# voltage_meas.net
KiCad netlist of a schematic drawn in EAGLE
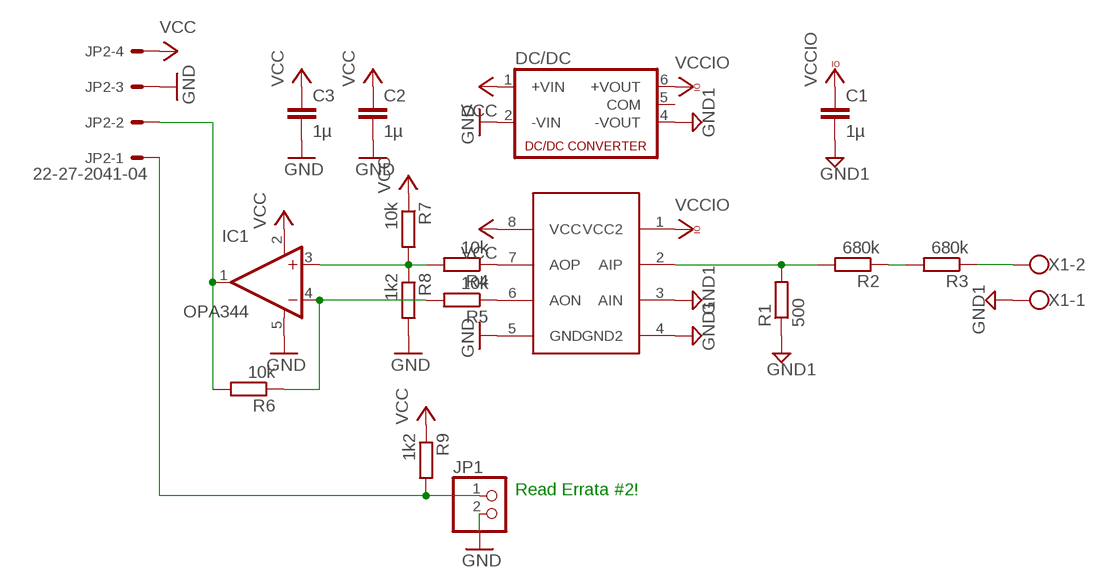
[diagram p0: schematic, sheet 1]

(export (version "E")
  (design (tool "Eeschema 10.0.6"))
  (components
    (comp (ref "C1")
      (value "1µ")
      (footprint "eagle-import:C025-024X044")
      (libsource (lib "eagle-import") (part "C-EU025-024X044"))
    )
    (comp (ref "C2")
      (value "1µ")
      (footprint "eagle-import:C025-024X044")
      (libsource (lib "eagle-import") (part "C-EU025-024X044"))
    )
    (comp (ref "C3")
      (value "1µ")
      (footprint "eagle-import:C025-024X044")
      (libsource (lib "eagle-import") (part "C-EU025-024X044"))
    )
    (comp (ref "DC/DC")
      (value "MEV3")
      (footprint "eagle-import:NMA")
      (libsource (lib "eagle-import") (part "MEV3"))
    )
    (comp (ref "IC1")
      (value "OPA344")
      (footprint "eagle-import:SOT23-5")
      (libsource (lib "eagle-import") (part "OPA344"))
    )
    (comp (ref "IC2")
      (value "SI8920")
      (footprint "eagle-import:DIP8")
      (libsource (lib "eagle-import") (part "SI8920"))
    )
    (comp (ref "JP1")
      (value "PINHD-1X2")
      (footprint "eagle-import:1X02")
      (libsource (lib "eagle-import") (part "PINHD-1X2"))
    )
    (comp (ref "JP2")
      (value "22-27-2041-04")
      (footprint "eagle-import:6410-04")
      (libsource (lib "eagle-import") (part "22-?-0427-2041"))
    )
    (comp (ref "R1")
      (value "500")
      (footprint "eagle-import:0207_10")
      (libsource (lib "eagle-import") (part "R-EU_0207/10"))
    )
    (comp (ref "R2")
      (value "680k")
      (footprint "eagle-import:0207_10")
      (libsource (lib "eagle-import") (part "R-EU_0207/10"))
    )
    (comp (ref "R3")
      (value "680k")
      (footprint "eagle-import:0207_10")
      (libsource (lib "eagle-import") (part "R-EU_0207/10"))
    )
    (comp (ref "R4")
      (value "10k")
      (footprint "eagle-import:0207_10")
      (libsource (lib "eagle-import") (part "R-EU_0207/10"))
    )
    (comp (ref "R5")
      (value "10k")
      (footprint "eagle-import:0207_10")
      (libsource (lib "eagle-import") (part "R-EU_0207/10"))
    )
    (comp (ref "R6")
      (value "10k")
      (footprint "eagle-import:0207_10")
      (libsource (lib "eagle-import") (part "R-EU_0207/10"))
    )
    (comp (ref "R7")
      (value "10k")
      (footprint "eagle-import:0207_10")
      (libsource (lib "eagle-import") (part "R-EU_0207/10"))
    )
    (comp (ref "R8")
      (value "1k2")
      (footprint "eagle-import:0207_10")
      (libsource (lib "eagle-import") (part "R-EU_0207/10"))
    )
    (comp (ref "R9")
      (value "1k2")
      (footprint "eagle-import:0207_10")
      (libsource (lib "eagle-import") (part "R-EU_0207/10"))
    )
    (comp (ref "X1")
      (value "W237-102")
      (footprint "eagle-import:W237-102")
      (fields (field (name "MPN") "237-102"))
      (libsource (lib "eagle-import") (part "W237-102"))
    )
  )
  (nets
    (net (code "1") (name "GND") (class "Default")
      (node (ref "C2") (pin "2") (pinfunction "2_2") (pintype "passive"))
      (node (ref "C3") (pin "2") (pinfunction "2_2") (pintype "passive"))
      (node (ref "DC/DC") (pin "2") (pinfunction "-VIN_2") (pintype "passive"))
      (node (ref "IC1") (pin "5") (pinfunction "V+_5") (pintype "power_in"))
      (node (ref "IC2") (pin "5") (pinfunction "GND_5") (pintype "bidirectional"))
      (node (ref "JP1") (pin "2") (pinfunction "2_2") (pintype "passive"))
      (node (ref "JP2") (pin "3") (pinfunction "S_3") (pintype "passive"))
      (node (ref "R8") (pin "2") (pinfunction "2_2") (pintype "passive"))
    )
    (net (code "2") (name "GND1") (class "Default")
      (node (ref "C1") (pin "2") (pinfunction "2_2") (pintype "passive"))
      (node (ref "DC/DC") (pin "4") (pinfunction "-VOUT_4") (pintype "passive"))
      (node (ref "IC2") (pin "3") (pinfunction "AIN_3") (pintype "bidirectional"))
      (node (ref "IC2") (pin "4") (pinfunction "GND2_4") (pintype "bidirectional"))
      (node (ref "R1") (pin "1") (pinfunction "1_1") (pintype "passive"))
      (node (ref "X1") (pin "1") (pinfunction "KL_1") (pintype "passive"))
    )
    (net (code "3") (name "Net-(IC1-+IN)") (class "Default")
      (node (ref "IC1") (pin "3") (pinfunction "+IN_3") (pintype "input"))
      (node (ref "R4") (pin "2") (pinfunction "2_2") (pintype "passive"))
      (node (ref "R7") (pin "2") (pinfunction "2_2") (pintype "passive"))
      (node (ref "R8") (pin "1") (pinfunction "1_1") (pintype "passive"))
    )
    (net (code "4") (name "Net-(IC1--IN)") (class "Default")
      (node (ref "IC1") (pin "4") (pinfunction "-IN_4") (pintype "input"))
      (node (ref "R5") (pin "2") (pinfunction "2_2") (pintype "passive"))
      (node (ref "R6") (pin "1") (pinfunction "1_1") (pintype "passive"))
    )
    (net (code "5") (name "Net-(IC1-OUT)") (class "Default")
      (node (ref "IC1") (pin "1") (pinfunction "OUT_1") (pintype "output"))
      (node (ref "JP2") (pin "2") (pinfunction "S_2") (pintype "passive"))
      (node (ref "R6") (pin "2") (pinfunction "2_2") (pintype "passive"))
    )
    (net (code "6") (name "Net-(IC2-AIP)") (class "Default")
      (node (ref "IC2") (pin "2") (pinfunction "AIP_2") (pintype "bidirectional"))
      (node (ref "R1") (pin "2") (pinfunction "2_2") (pintype "passive"))
      (node (ref "R2") (pin "2") (pinfunction "2_2") (pintype "passive"))
    )
    (net (code "7") (name "Net-(IC2-AON)") (class "Default")
      (node (ref "IC2") (pin "6") (pinfunction "AON_6") (pintype "bidirectional"))
      (node (ref "R5") (pin "1") (pinfunction "1_1") (pintype "passive"))
    )
    (net (code "8") (name "Net-(IC2-AOP)") (class "Default")
      (node (ref "IC2") (pin "7") (pinfunction "AOP_7") (pintype "bidirectional"))
      (node (ref "R4") (pin "1") (pinfunction "1_1") (pintype "passive"))
    )
    (net (code "9") (name "Net-(JP2A-S)") (class "Default")
      (node (ref "JP1") (pin "1") (pinfunction "1_1") (pintype "passive"))
      (node (ref "JP2") (pin "1") (pinfunction "S_1") (pintype "passive"))
      (node (ref "R9") (pin "2") (pinfunction "2_2") (pintype "passive"))
    )
    (net (code "10") (name "Net-(R2-Pad1)") (class "Default")
      (node (ref "R2") (pin "1") (pinfunction "1_1") (pintype "passive"))
      (node (ref "R3") (pin "2") (pinfunction "2_2") (pintype "passive"))
    )
    (net (code "11") (name "Net-(X1B-KL)") (class "Default")
      (node (ref "R3") (pin "1") (pinfunction "1_1") (pintype "passive"))
      (node (ref "X1") (pin "2") (pinfunction "KL_2") (pintype "passive"))
    )
    (net (code "12") (name "VCC") (class "Default")
      (node (ref "C2") (pin "1") (pinfunction "1_1") (pintype "passive"))
      (node (ref "C3") (pin "1") (pinfunction "1_1") (pintype "passive"))
      (node (ref "DC/DC") (pin "1") (pinfunction "+VIN_1") (pintype "passive"))
      (node (ref "IC1") (pin "2") (pinfunction "V-_2") (pintype "power_in"))
      (node (ref "IC2") (pin "8") (pinfunction "VCC_8") (pintype "bidirectional"))
      (node (ref "JP2") (pin "4") (pinfunction "S_4") (pintype "passive"))
      (node (ref "R7") (pin "1") (pinfunction "1_1") (pintype "passive"))
      (node (ref "R9") (pin "1") (pinfunction "1_1") (pintype "passive"))
    )
    (net (code "13") (name "VCCIO") (class "Default")
      (node (ref "C1") (pin "1") (pinfunction "1_1") (pintype "passive"))
      (node (ref "DC/DC") (pin "6") (pinfunction "+VOUT_6") (pintype "passive"))
      (node (ref "IC2") (pin "1") (pinfunction "VCC2_1") (pintype "bidirectional"))
    )
    (net (code "14") (name "unconnected-(DC/DC-COM-Pad5)") (class "Default")
      (node (ref "DC/DC") (pin "5") (pinfunction "COM_5") (pintype "passive"))
    )
  )
)
